# rtc_ds3212_shield.net
KiCad netlist of a schematic drawn in EAGLE
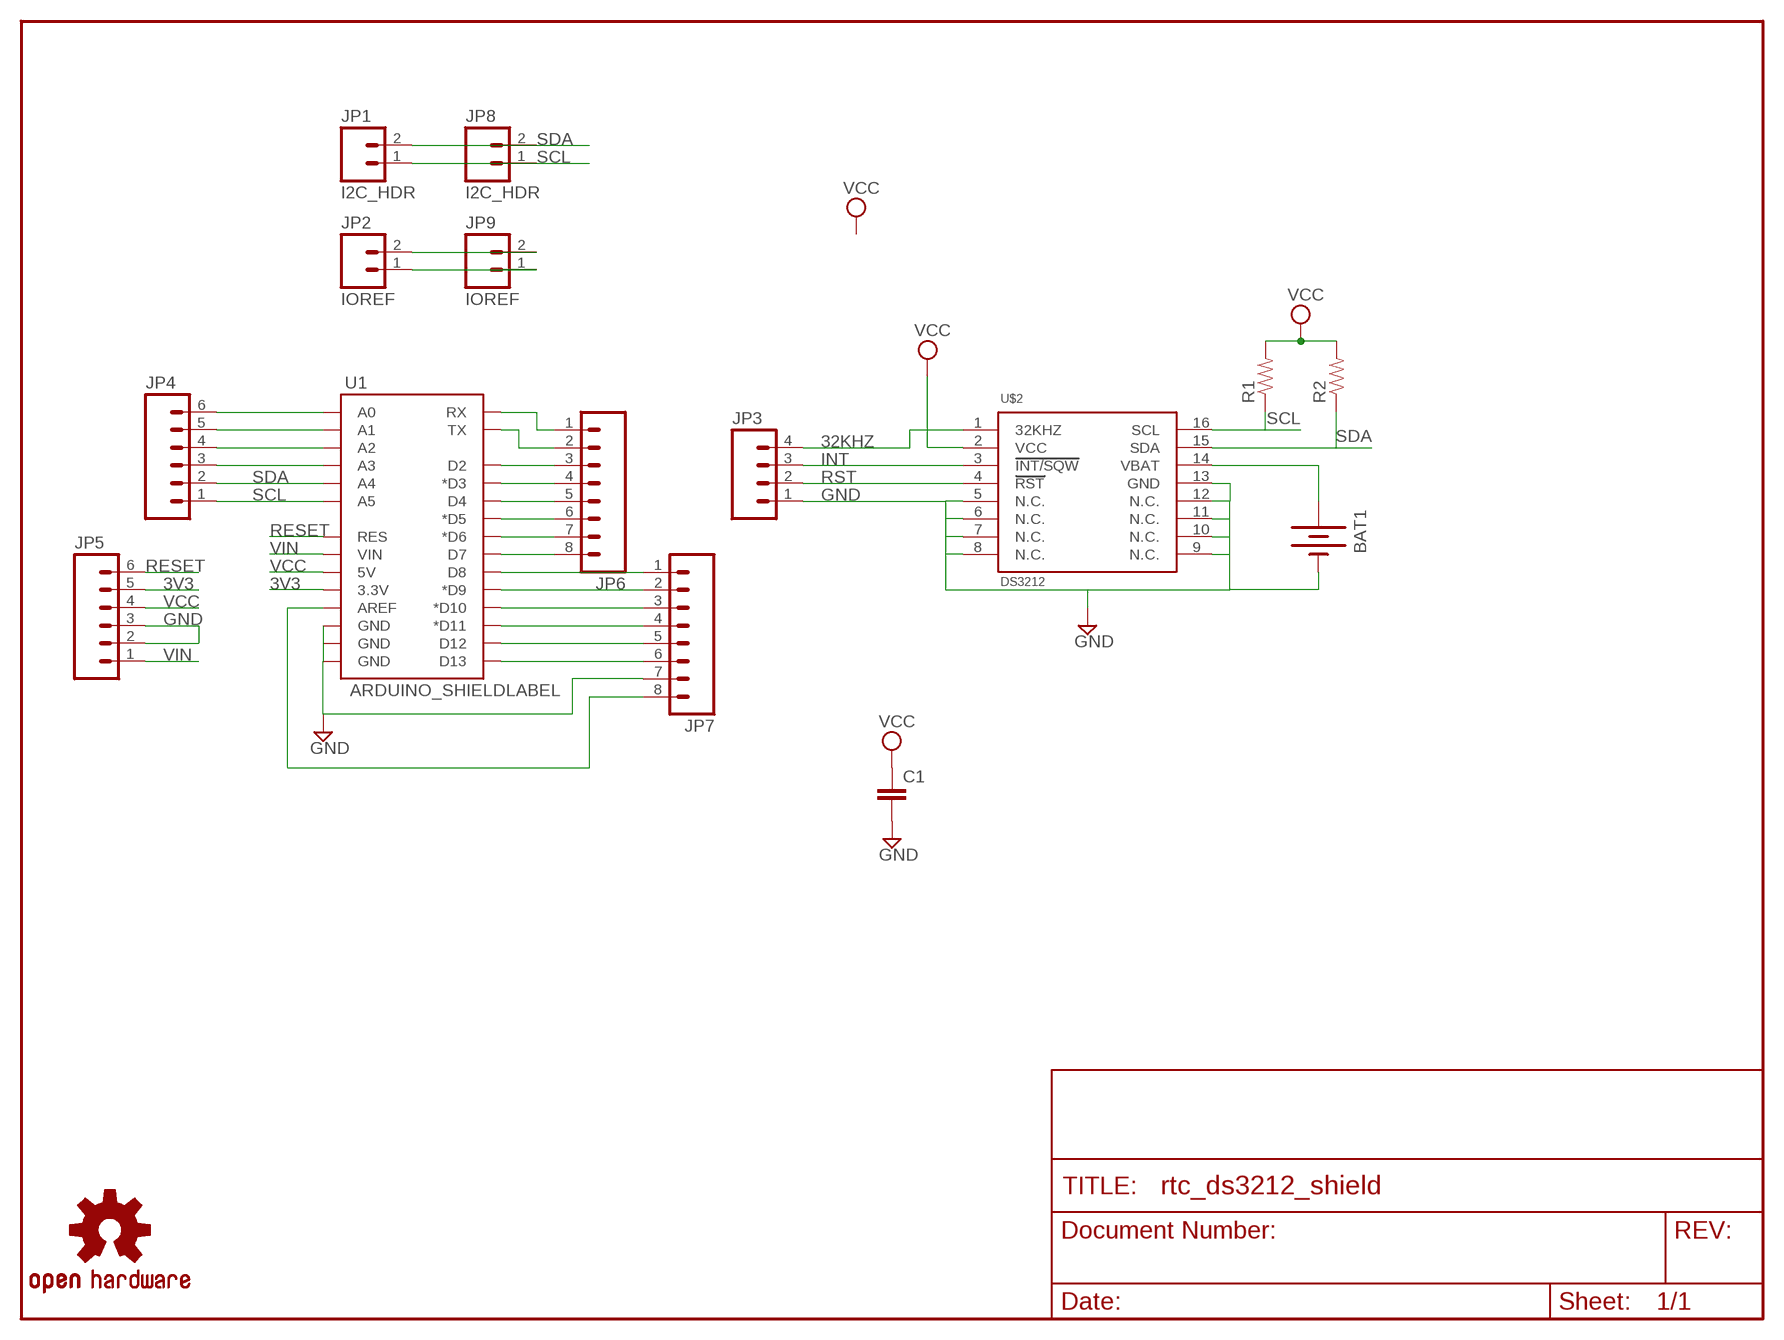
[diagram p0: schematic, sheet 1]

(export (version "E")
  (design (tool "Eeschema 10.0.6"))
  (components
    (comp (ref "BAT1")
      (value "BATTERY12MM")
      (footprint "eagle-import:BATTCON_12MM")
      (libsource (lib "eagle-import") (part "BATTERY12MM"))
    )
    (comp (ref "C1")
      (value "CAP1206")
      (footprint "eagle-import:1206")
      (libsource (lib "eagle-import") (part "CAP1206"))
    )
    (comp (ref "JP1")
      (value "I2C_HDR")
      (footprint "eagle-import:1X02")
      (libsource (lib "eagle-import") (part "M02PTH"))
    )
    (comp (ref "JP2")
      (value "IOREF")
      (footprint "eagle-import:1X02")
      (libsource (lib "eagle-import") (part "M02PTH"))
    )
    (comp (ref "JP3")
      (value "M04PTH")
      (footprint "eagle-import:1X04")
      (libsource (lib "eagle-import") (part "M04PTH"))
    )
    (comp (ref "JP4")
      (value "M06SIP")
      (footprint "eagle-import:1X06")
      (libsource (lib "eagle-import") (part "M06SIP"))
    )
    (comp (ref "JP5")
      (value "M06SIP")
      (footprint "eagle-import:1X06")
      (libsource (lib "eagle-import") (part "M06SIP"))
    )
    (comp (ref "JP6")
      (value "M081X08")
      (footprint "eagle-import:1X08")
      (libsource (lib "eagle-import") (part "M081X08"))
    )
    (comp (ref "JP7")
      (value "M081X08")
      (footprint "eagle-import:1X08")
      (libsource (lib "eagle-import") (part "M081X08"))
    )
    (comp (ref "JP8")
      (value "I2C_HDR")
      (footprint "eagle-import:1X02")
      (libsource (lib "eagle-import") (part "M02PTH"))
    )
    (comp (ref "JP9")
      (value "IOREF")
      (footprint "eagle-import:1X02")
      (libsource (lib "eagle-import") (part "M02PTH"))
    )
    (comp (ref "R1")
      (value "RESISTOR1206")
      (footprint "eagle-import:1206")
      (libsource (lib "eagle-import") (part "RESISTOR1206"))
    )
    (comp (ref "R2")
      (value "RESISTOR1206")
      (footprint "eagle-import:1206")
      (libsource (lib "eagle-import") (part "RESISTOR1206"))
    )
    (comp (ref "U$1")
      (value "OSHW-LOGOM")
      (footprint "eagle-import:OSHW-LOGO-M")
      (libsource (lib "eagle-import") (part "OSHW-LOGOM"))
    )
    (comp (ref "U$2")
      (value "DS3212")
      (footprint "eagle-import:SO16L")
      (libsource (lib "eagle-import") (part "DS3231"))
    )
    (comp (ref "U1")
      (value "ARDUINO_SHIELDLABEL")
      (footprint "eagle-import:UNOR3_SHIELD")
      (libsource (lib "eagle-import") (part "ARDUINO_SHIELDLABEL"))
    )
  )
  (nets
    (net (code "1") (name "/3V3") (class "Default")
      (node (ref "JP5") (pin "5") (pinfunction "5_5") (pintype "passive"))
      (node (ref "U1") (pin "3.3V") (pinfunction "3.3V_3.3V") (pintype "bidirectional"))
    )
    (net (code "2") (name "/32KHZ") (class "Default")
      (node (ref "JP3") (pin "4") (pinfunction "4_4") (pintype "passive"))
      (node (ref "U$2") (pin "1") (pinfunction "32KHZ_1") (pintype "bidirectional"))
    )
    (net (code "3") (name "/INT") (class "Default")
      (node (ref "JP3") (pin "3") (pinfunction "3_3") (pintype "passive"))
      (node (ref "U$2") (pin "3") (pinfunction "INT/SQW_3") (pintype "bidirectional"))
    )
    (net (code "4") (name "/RESET") (class "Default")
      (node (ref "JP5") (pin "6") (pinfunction "6_6") (pintype "passive"))
      (node (ref "U1") (pin "RES") (pinfunction "RES_RES") (pintype "bidirectional"))
    )
    (net (code "5") (name "/RST") (class "Default")
      (node (ref "JP3") (pin "2") (pinfunction "2_2") (pintype "passive"))
      (node (ref "U$2") (pin "4") (pinfunction "RST_4") (pintype "bidirectional"))
    )
    (net (code "6") (name "/SCL") (class "Default")
      (node (ref "JP1") (pin "1") (pinfunction "1_1") (pintype "passive"))
      (node (ref "JP4") (pin "1") (pinfunction "1_1") (pintype "passive"))
      (node (ref "JP8") (pin "1") (pinfunction "1_1") (pintype "passive"))
      (node (ref "R1") (pin "1") (pinfunction "1_1") (pintype "passive"))
      (node (ref "U$2") (pin "16") (pinfunction "SCL_16") (pintype "bidirectional"))
      (node (ref "U1") (pin "A5") (pinfunction "A5_A5") (pintype "bidirectional"))
    )
    (net (code "7") (name "/SDA") (class "Default")
      (node (ref "JP1") (pin "2") (pinfunction "2_2") (pintype "passive"))
      (node (ref "JP4") (pin "2") (pinfunction "2_2") (pintype "passive"))
      (node (ref "JP8") (pin "2") (pinfunction "2_2") (pintype "passive"))
      (node (ref "R2") (pin "1") (pinfunction "1_1") (pintype "passive"))
      (node (ref "U$2") (pin "15") (pinfunction "SDA_15") (pintype "bidirectional"))
      (node (ref "U1") (pin "A4") (pinfunction "A4_A4") (pintype "bidirectional"))
    )
    (net (code "8") (name "/VIN") (class "Default")
      (node (ref "JP5") (pin "1") (pinfunction "1_1") (pintype "passive"))
      (node (ref "U1") (pin "VIN") (pinfunction "VIN_VIN") (pintype "bidirectional"))
    )
    (net (code "9") (name "GND") (class "Default")
      (node (ref "BAT1") (pin "GND") (pinfunction "-_GND") (pintype "power_in"))
      (node (ref "C1") (pin "2") (pinfunction "2_2") (pintype "passive"))
      (node (ref "JP3") (pin "1") (pinfunction "1_1") (pintype "passive"))
      (node (ref "JP5") (pin "2") (pinfunction "2_2") (pintype "passive"))
      (node (ref "JP5") (pin "3") (pinfunction "3_3") (pintype "passive"))
      (node (ref "JP7") (pin "7") (pinfunction "7_7") (pintype "passive"))
      (node (ref "U$2") (pin "10") (pinfunction "N.C._10") (pintype "bidirectional"))
      (node (ref "U$2") (pin "11") (pinfunction "N.C._11") (pintype "bidirectional"))
      (node (ref "U$2") (pin "12") (pinfunction "N.C._12") (pintype "bidirectional"))
      (node (ref "U$2") (pin "13") (pinfunction "GND_13") (pintype "power_in"))
      (node (ref "U$2") (pin "5") (pinfunction "N.C._5") (pintype "bidirectional"))
      (node (ref "U$2") (pin "6") (pinfunction "N.C._6") (pintype "bidirectional"))
      (node (ref "U$2") (pin "7") (pinfunction "N.C._7") (pintype "bidirectional"))
      (node (ref "U$2") (pin "8") (pinfunction "N.C._8") (pintype "bidirectional"))
      (node (ref "U$2") (pin "9") (pinfunction "N.C._9") (pintype "bidirectional"))
      (node (ref "U1") (pin "GND@0") (pinfunction "GND_GND@0") (pintype "bidirectional"))
      (node (ref "U1") (pin "GND@1") (pinfunction "GND_GND@1") (pintype "bidirectional"))
      (node (ref "U1") (pin "GND@2") (pinfunction "GND_GND@2") (pintype "bidirectional"))
    )
    (net (code "10") (name "Net-(BAT1-+)") (class "Default")
      (node (ref "BAT1") (pin "PWR@2") (pinfunction "+_PWR@2") (pintype "power_in"))
      (node (ref "U$2") (pin "14") (pinfunction "VBAT_14") (pintype "power_in"))
    )
    (net (code "11") (name "Net-(JP2-Pad1)") (class "Default")
      (node (ref "JP2") (pin "1") (pinfunction "1_1") (pintype "passive"))
      (node (ref "JP9") (pin "1") (pinfunction "1_1") (pintype "passive"))
    )
    (net (code "12") (name "Net-(JP2-Pad2)") (class "Default")
      (node (ref "JP2") (pin "2") (pinfunction "2_2") (pintype "passive"))
      (node (ref "JP9") (pin "2") (pinfunction "2_2") (pintype "passive"))
    )
    (net (code "13") (name "Net-(JP4-Pad3)") (class "Default")
      (node (ref "JP4") (pin "3") (pinfunction "3_3") (pintype "passive"))
      (node (ref "U1") (pin "A3") (pinfunction "A3_A3") (pintype "bidirectional"))
    )
    (net (code "14") (name "Net-(JP4-Pad4)") (class "Default")
      (node (ref "JP4") (pin "4") (pinfunction "4_4") (pintype "passive"))
      (node (ref "U1") (pin "A2") (pinfunction "A2_A2") (pintype "bidirectional"))
    )
    (net (code "15") (name "Net-(JP4-Pad5)") (class "Default")
      (node (ref "JP4") (pin "5") (pinfunction "5_5") (pintype "passive"))
      (node (ref "U1") (pin "A1") (pinfunction "A1_A1") (pintype "bidirectional"))
    )
    (net (code "16") (name "Net-(JP4-Pad6)") (class "Default")
      (node (ref "JP4") (pin "6") (pinfunction "6_6") (pintype "passive"))
      (node (ref "U1") (pin "A0") (pinfunction "A0_A0") (pintype "bidirectional"))
    )
    (net (code "17") (name "Net-(JP6-Pad1)") (class "Default")
      (node (ref "JP6") (pin "1") (pinfunction "1_1") (pintype "passive"))
      (node (ref "U1") (pin "RX") (pinfunction "RX_RX") (pintype "bidirectional"))
    )
    (net (code "18") (name "Net-(JP6-Pad2)") (class "Default")
      (node (ref "JP6") (pin "2") (pinfunction "2_2") (pintype "passive"))
      (node (ref "U1") (pin "TX") (pinfunction "TX_TX") (pintype "bidirectional"))
    )
    (net (code "19") (name "Net-(JP6-Pad3)") (class "Default")
      (node (ref "JP6") (pin "3") (pinfunction "3_3") (pintype "passive"))
      (node (ref "U1") (pin "D2") (pinfunction "D2_D2") (pintype "bidirectional"))
    )
    (net (code "20") (name "Net-(JP6-Pad5)") (class "Default")
      (node (ref "JP6") (pin "5") (pinfunction "5_5") (pintype "passive"))
      (node (ref "U1") (pin "D4") (pinfunction "D4_D4") (pintype "bidirectional"))
    )
    (net (code "21") (name "Net-(JP6-Pad8)") (class "Default")
      (node (ref "JP6") (pin "8") (pinfunction "8_8") (pintype "passive"))
      (node (ref "U1") (pin "D7") (pinfunction "D7_D7") (pintype "bidirectional"))
    )
    (net (code "22") (name "Net-(JP7-Pad1)") (class "Default")
      (node (ref "JP7") (pin "1") (pinfunction "1_1") (pintype "passive"))
      (node (ref "U1") (pin "D8") (pinfunction "D8_D8") (pintype "bidirectional"))
    )
    (net (code "23") (name "Net-(JP7-Pad5)") (class "Default")
      (node (ref "JP7") (pin "5") (pinfunction "5_5") (pintype "passive"))
      (node (ref "U1") (pin "D12") (pinfunction "D12_D12") (pintype "bidirectional"))
    )
    (net (code "24") (name "Net-(JP7-Pad6)") (class "Default")
      (node (ref "JP7") (pin "6") (pinfunction "6_6") (pintype "passive"))
      (node (ref "U1") (pin "D13") (pinfunction "D13_D13") (pintype "bidirectional"))
    )
    (net (code "25") (name "Net-(JP7-Pad8)") (class "Default")
      (node (ref "JP7") (pin "8") (pinfunction "8_8") (pintype "passive"))
      (node (ref "U1") (pin "AREF") (pinfunction "AREF_AREF") (pintype "bidirectional"))
    )
    (net (code "26") (name "Net-(U1-*D3)") (class "Default")
      (node (ref "JP6") (pin "4") (pinfunction "4_4") (pintype "passive"))
      (node (ref "U1") (pin "D3") (pinfunction "*D3_D3") (pintype "bidirectional"))
    )
    (net (code "27") (name "Net-(U1-*D5)") (class "Default")
      (node (ref "JP6") (pin "6") (pinfunction "6_6") (pintype "passive"))
      (node (ref "U1") (pin "D5") (pinfunction "*D5_D5") (pintype "bidirectional"))
    )
    (net (code "28") (name "Net-(U1-*D6)") (class "Default")
      (node (ref "JP6") (pin "7") (pinfunction "7_7") (pintype "passive"))
      (node (ref "U1") (pin "D6") (pinfunction "*D6_D6") (pintype "bidirectional"))
    )
    (net (code "29") (name "Net-(U1-*D9)") (class "Default")
      (node (ref "JP7") (pin "2") (pinfunction "2_2") (pintype "passive"))
      (node (ref "U1") (pin "D9") (pinfunction "*D9_D9") (pintype "bidirectional"))
    )
    (net (code "30") (name "Net-(U1-*D10)") (class "Default")
      (node (ref "JP7") (pin "3") (pinfunction "3_3") (pintype "passive"))
      (node (ref "U1") (pin "D10") (pinfunction "*D10_D10") (pintype "bidirectional"))
    )
    (net (code "31") (name "Net-(U1-*D11)") (class "Default")
      (node (ref "JP7") (pin "4") (pinfunction "4_4") (pintype "passive"))
      (node (ref "U1") (pin "D11") (pinfunction "*D11_D11") (pintype "bidirectional"))
    )
    (net (code "32") (name "VCC") (class "Default")
      (node (ref "C1") (pin "1") (pinfunction "1_1") (pintype "passive"))
      (node (ref "JP5") (pin "4") (pinfunction "4_4") (pintype "passive"))
      (node (ref "R1") (pin "2") (pinfunction "2_2") (pintype "passive"))
      (node (ref "R2") (pin "2") (pinfunction "2_2") (pintype "passive"))
      (node (ref "U$2") (pin "2") (pinfunction "VCC_2") (pintype "power_in"))
      (node (ref "U1") (pin "5V") (pinfunction "5V_5V") (pintype "bidirectional"))
    )
  )
)
